# TC364_MainBoard_Power_V2_0.net
KiCad netlist of a schematic drawn in Altium Designer
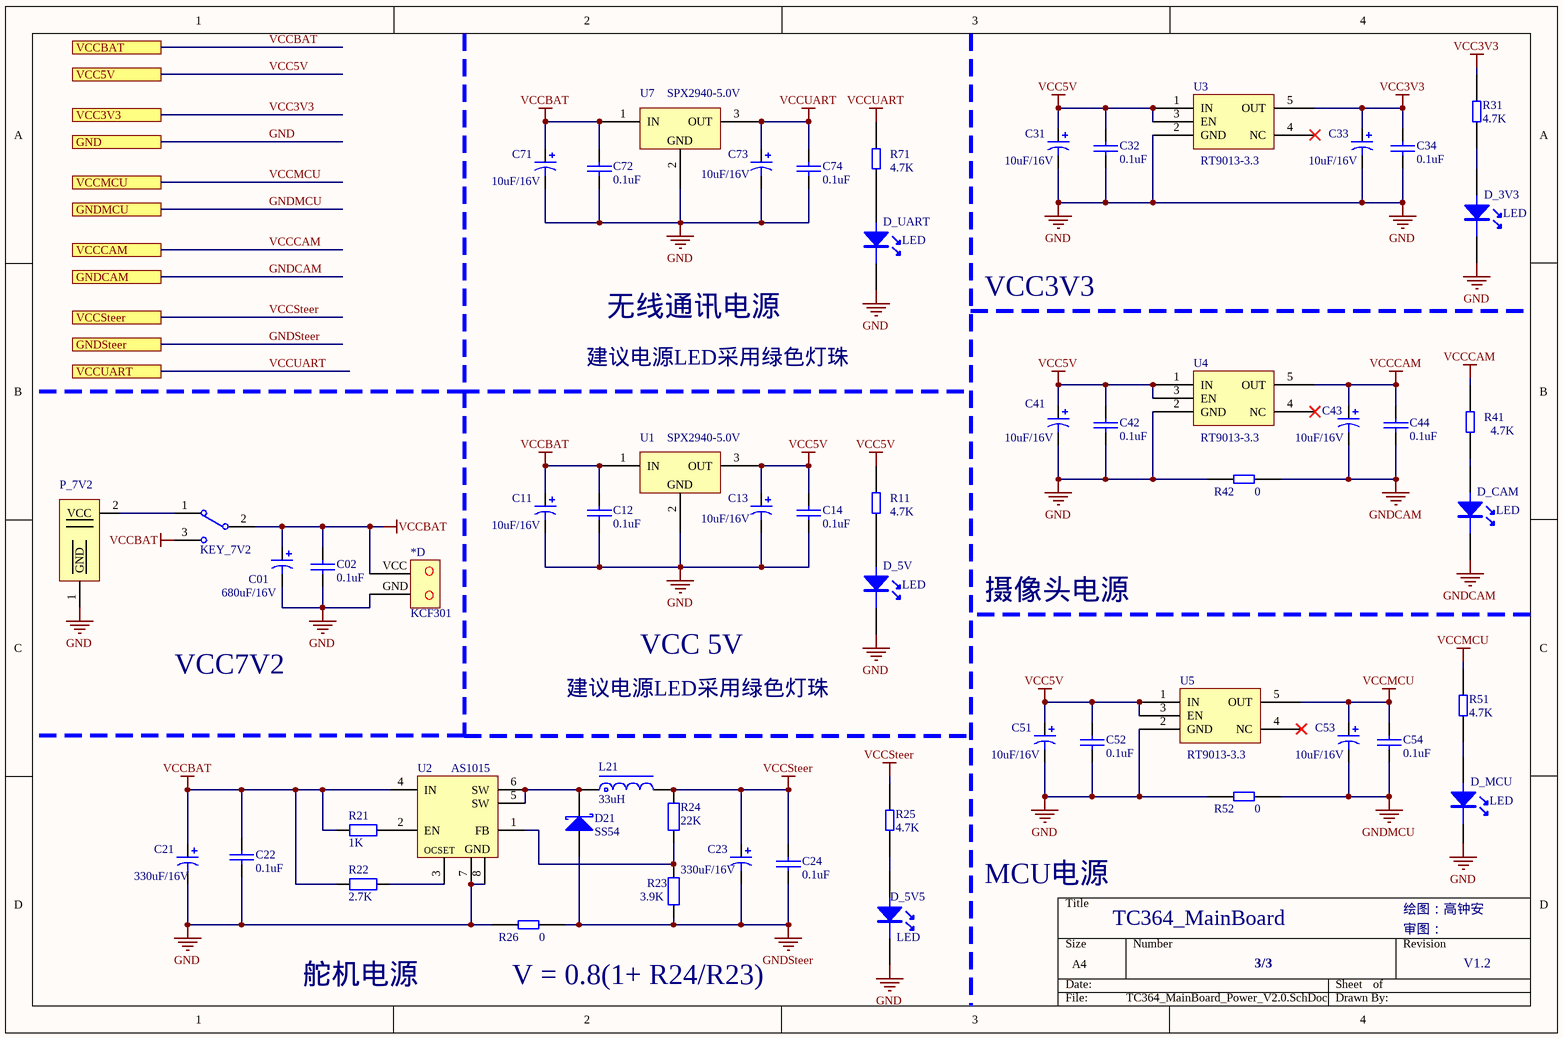
[diagram p0: TC364_MainBoard_Power_V2.0.SchDoc]

(export (version "E")
  (design (tool "Eeschema 10.0.6"))
  (components
    (comp (ref "*") (value "KCF301") (footprint "KF301-2P") (libsource (lib "BaseLib_SCH") (part "KCF301")))
    (comp (ref "C01")
      (value "680uF/16V")
      (footprint "CAP 3.5*8*11.5 - GD")
      (description "Polarized Capacitor (Radial)")
      (fields (field (name "PUBLISHER") "Altium Limited"))
      (libsource (lib "Miscellaneous Devices") (part "Cap Pol1"))
    )
    (comp (ref "C02")
      (value "0.1uF")
      (footprint "0805C")
      (description "Capacitor")
      (libsource (lib "Protel99Lib_SCH") (part "CAP"))
    )
    (comp (ref "C11")
      (value "10uF/16V")
      (footprint "CASE-A_3216")
      (description "Polarized Capacitor (Radial)")
      (fields (field (name "PUBLISHER") "Altium Limited"))
      (libsource (lib "Miscellaneous Devices") (part "Cap Pol1"))
    )
    (comp (ref "C12")
      (value "0.1uF")
      (footprint "0805C")
      (description "Capacitor")
      (libsource (lib "Protel99Lib_SCH") (part "CAP"))
    )
    (comp (ref "C13")
      (value "10uF/16V")
      (footprint "CASE-A_3216")
      (description "Polarized Capacitor (Radial)")
      (fields (field (name "PUBLISHER") "Altium Limited"))
      (libsource (lib "Miscellaneous Devices") (part "Cap Pol1"))
    )
    (comp (ref "C14")
      (value "0.1uF")
      (footprint "0805C")
      (description "Capacitor")
      (libsource (lib "Protel99Lib_SCH") (part "CAP"))
    )
    (comp (ref "C21")
      (value "330uF/16V")
      (footprint "CAP 2.5*6.3*11.2 - BK")
      (description "Polarized Capacitor (Radial)")
      (fields (field (name "PUBLISHER") "Altium Limited"))
      (libsource (lib "Miscellaneous Devices") (part "Cap Pol1"))
    )
    (comp (ref "C22")
      (value "0.1uF")
      (footprint "0805C")
      (description "Capacitor")
      (libsource (lib "Protel99Lib_SCH") (part "CAP"))
    )
    (comp (ref "C23")
      (value "330uF/16V")
      (footprint "CAP 2.5*6.3*11.2 - BK")
      (description "Polarized Capacitor (Radial)")
      (fields (field (name "PUBLISHER") "Altium Limited"))
      (libsource (lib "Miscellaneous Devices") (part "Cap Pol1"))
    )
    (comp (ref "C24")
      (value "0.1uF")
      (footprint "0805C")
      (description "Capacitor")
      (libsource (lib "Protel99Lib_SCH") (part "CAP"))
    )
    (comp (ref "C31")
      (value "10uF/16V")
      (footprint "CASE-A_3216")
      (description "Polarized Capacitor (Radial)")
      (fields (field (name "PUBLISHER") "Altium Limited"))
      (libsource (lib "Miscellaneous Devices") (part "Cap Pol1"))
    )
    (comp (ref "C32")
      (value "0.1uF")
      (footprint "0805C")
      (description "Capacitor")
      (libsource (lib "Protel99Lib_SCH") (part "CAP"))
    )
    (comp (ref "C33")
      (value "10uF/16V")
      (footprint "CASE-A_3216")
      (description "Polarized Capacitor (Radial)")
      (fields (field (name "PUBLISHER") "Altium Limited"))
      (libsource (lib "Miscellaneous Devices") (part "Cap Pol1"))
    )
    (comp (ref "C34")
      (value "0.1uF")
      (footprint "0805C")
      (description "Capacitor")
      (libsource (lib "Protel99Lib_SCH") (part "CAP"))
    )
    (comp (ref "C41")
      (value "10uF/16V")
      (footprint "CASE-A_3216")
      (description "Polarized Capacitor (Radial)")
      (fields (field (name "PUBLISHER") "Altium Limited"))
      (libsource (lib "Miscellaneous Devices") (part "Cap Pol1"))
    )
    (comp (ref "C42")
      (value "0.1uF")
      (footprint "0805C")
      (description "Capacitor")
      (libsource (lib "Protel99Lib_SCH") (part "CAP"))
    )
    (comp (ref "C43")
      (value "10uF/16V")
      (footprint "CASE-A_3216")
      (description "Polarized Capacitor (Radial)")
      (fields (field (name "PUBLISHER") "Altium Limited"))
      (libsource (lib "Miscellaneous Devices") (part "Cap Pol1"))
    )
    (comp (ref "C44")
      (value "0.1uF")
      (footprint "0805C")
      (description "Capacitor")
      (libsource (lib "Protel99Lib_SCH") (part "CAP"))
    )
    (comp (ref "C51")
      (value "10uF/16V")
      (footprint "CASE-A_3216")
      (description "Polarized Capacitor (Radial)")
      (fields (field (name "PUBLISHER") "Altium Limited"))
      (libsource (lib "Miscellaneous Devices") (part "Cap Pol1"))
    )
    (comp (ref "C52")
      (value "0.1uF")
      (footprint "0805C")
      (description "Capacitor")
      (libsource (lib "Protel99Lib_SCH") (part "CAP"))
    )
    (comp (ref "C53")
      (value "10uF/16V")
      (footprint "CASE-A_3216")
      (description "Polarized Capacitor (Radial)")
      (fields (field (name "PUBLISHER") "Altium Limited"))
      (libsource (lib "Miscellaneous Devices") (part "Cap Pol1"))
    )
    (comp (ref "C54")
      (value "0.1uF")
      (footprint "0805C")
      (description "Capacitor")
      (libsource (lib "Protel99Lib_SCH") (part "CAP"))
    )
    (comp (ref "C71")
      (value "10uF/16V")
      (footprint "CASE-A_3216")
      (description "Polarized Capacitor (Radial)")
      (fields (field (name "PUBLISHER") "Altium Limited"))
      (libsource (lib "Miscellaneous Devices") (part "Cap Pol1"))
    )
    (comp (ref "C72")
      (value "0.1uF")
      (footprint "0805C")
      (description "Capacitor")
      (libsource (lib "Protel99Lib_SCH") (part "CAP"))
    )
    (comp (ref "C73")
      (value "10uF/16V")
      (footprint "CASE-A_3216")
      (description "Polarized Capacitor (Radial)")
      (fields (field (name "PUBLISHER") "Altium Limited"))
      (libsource (lib "Miscellaneous Devices") (part "Cap Pol1"))
    )
    (comp (ref "C74")
      (value "0.1uF")
      (footprint "0805C")
      (description "Capacitor")
      (libsource (lib "Protel99Lib_SCH") (part "CAP"))
    )
    (comp (ref "D21")
      (value "SS54")
      (footprint "SMA")
      (description "肖特基二极管")
      (libsource (lib "0.2 -  二极管-整流桥") (part "SS34"))
    )
    (comp (ref "D_3V3")
      (value "LED")
      (footprint "0805_LED_S1")
      (description "发光二极管")
      (libsource (lib "jianing") (part "LED"))
    )
    (comp (ref "D_5V")
      (value "LED")
      (footprint "0805_LED_S1")
      (description "发光二极管")
      (libsource (lib "jianing") (part "LED"))
    )
    (comp (ref "D_5V5")
      (value "LED")
      (footprint "0805_LED_S1")
      (description "发光二极管")
      (libsource (lib "jianing") (part "LED"))
    )
    (comp (ref "D_CAM")
      (value "LED")
      (footprint "0805_LED_S1")
      (description "发光二极管")
      (libsource (lib "jianing") (part "LED"))
    )
    (comp (ref "D_MCU")
      (value "LED")
      (footprint "0805_LED_S1")
      (description "发光二极管")
      (libsource (lib "jianing") (part "LED"))
    )
    (comp (ref "D_UART")
      (value "LED")
      (footprint "0805_LED_S1")
      (description "发光二极管")
      (libsource (lib "jianing") (part "LED"))
    )
    (comp (ref "KEY_7V2")
      (value "SS-12F23")
      (footprint "KEY_7V2")
      (description "1路波动开关")
      (fields (field (name "版权归属") "封装库来自淘宝 ID：黄晶宝石"))
      (libsource (lib "0.7 - 常用按键-开关") (part "SSW-1P"))
    )
    (comp (ref "L21")
      (value "33uH")
      (footprint "7*7 L")
      (description "功率屏蔽电感")
      (fields (field (name "版权归属") "封装库来自淘宝 ID：黄晶宝石"))
      (libsource (lib "0.1 - 电阻-电容-电感") (part "L-CDRH"))
    )
    (comp (ref "P_7V2")
      (value "T_Type_Adapter")
      (footprint "T_Type_Adapter")
      (libsource (lib "Schlib1") (part "T_Type_Adapter"))
    )
    (comp (ref "R11") (value "4.7K") (footprint "0805R") (libsource (lib "BaseLib_SCH") (part "RES")))
    (comp (ref "R21")
      (value "1K")
      (footprint "0805R")
      (description "贴片电阻")
      (fields (field (name "版权归属") "源创客"))
      (libsource (lib "jianing") (part "RES"))
    )
    (comp (ref "R22")
      (value "2.7K")
      (footprint "0805R")
      (description "贴片电阻")
      (fields (field (name "版权归属") "源创客"))
      (libsource (lib "jianing") (part "RES"))
    )
    (comp (ref "R23")
      (value "3.9K")
      (footprint "0805R")
      (description "贴片电阻")
      (fields (field (name "版权归属") "源创客"))
      (libsource (lib "jianing") (part "RES"))
    )
    (comp (ref "R24")
      (value "22K")
      (footprint "0805R")
      (description "贴片电阻")
      (fields (field (name "版权归属") "源创客"))
      (libsource (lib "jianing") (part "RES"))
    )
    (comp (ref "R25") (value "4.7K") (footprint "0805R") (libsource (lib "BaseLib_SCH") (part "RES")))
    (comp (ref "R26") (value "0") (footprint "0805R") (libsource (lib "BaseLib_SCH") (part "RES")))
    (comp (ref "R31") (value "4.7K") (footprint "0805R") (libsource (lib "BaseLib_SCH") (part "RES")))
    (comp (ref "R41") (value "4.7K") (footprint "0805R") (libsource (lib "BaseLib_SCH") (part "RES")))
    (comp (ref "R42") (value "0") (footprint "0805R") (libsource (lib "BaseLib_SCH") (part "RES")))
    (comp (ref "R51") (value "4.7K") (footprint "0805R") (libsource (lib "BaseLib_SCH") (part "RES")))
    (comp (ref "R52") (value "0") (footprint "0805R") (libsource (lib "BaseLib_SCH") (part "RES")))
    (comp (ref "R71") (value "4.7K") (footprint "0805R") (libsource (lib "BaseLib_SCH") (part "RES")))
    (comp (ref "U1")
      (value "SPX2940-5.0V")
      (footprint "TO-220(TO-220-3)")
      (description "5V稳压芯片")
      (fields (field (name "版权归属") "封装库来自淘宝 ID：黄晶宝石"))
      (libsource (lib "1.1 - 电源类芯片") (part "LM2940"))
    )
    (comp (ref "U2")
      (value "AS1015")
      (footprint "SOP-8_150mil")
      (description "可调升压芯片")
      (libsource (lib "1.0 - 常见芯片") (part "AS1015"))
    )
    (comp (ref "U3")
      (value "RT9013-3.3")
      (footprint "SOT-23-5")
      (libsource (lib "jianing") (part "RT9013-3.3"))
    )
    (comp (ref "U4")
      (value "RT9013-3.3")
      (footprint "SOT-23-5")
      (libsource (lib "jianing") (part "RT9013-3.3"))
    )
    (comp (ref "U5")
      (value "RT9013-3.3")
      (footprint "SOT-23-5")
      (libsource (lib "jianing") (part "RT9013-3.3"))
    )
    (comp (ref "U7")
      (value "SPX2940-5.0V")
      (footprint "TO-220(TO-220-3)")
      (description "5V稳压芯片")
      (fields (field (name "版权归属") "封装库来自淘宝 ID：黄晶宝石"))
      (libsource (lib "1.1 - 电源类芯片") (part "LM2940"))
    )
  )
  (nets
    (net (code "1") (name "GND") (class "Default")
      (node (ref "C01") (pin "2") (pinfunction "2_2") (pintype "passive"))
      (node (ref "C02") (pin "2") (pinfunction "2_2") (pintype "passive"))
      (node (ref "C11") (pin "2") (pinfunction "2_2") (pintype "passive"))
      (node (ref "C12") (pin "2") (pinfunction "2_2") (pintype "passive"))
      (node (ref "C13") (pin "2") (pinfunction "2_2") (pintype "passive"))
      (node (ref "C14") (pin "2") (pinfunction "2_2") (pintype "passive"))
      (node (ref "C21") (pin "2") (pinfunction "2_2") (pintype "passive"))
      (node (ref "C22") (pin "2") (pinfunction "2_2") (pintype "passive"))
      (node (ref "C31") (pin "2") (pinfunction "2_2") (pintype "passive"))
      (node (ref "C32") (pin "2") (pinfunction "2_2") (pintype "passive"))
      (node (ref "C33") (pin "2") (pinfunction "2_2") (pintype "passive"))
      (node (ref "C34") (pin "2") (pinfunction "2_2") (pintype "passive"))
      (node (ref "C41") (pin "2") (pinfunction "2_2") (pintype "passive"))
      (node (ref "C42") (pin "2") (pinfunction "2_2") (pintype "passive"))
      (node (ref "C51") (pin "2") (pinfunction "2_2") (pintype "passive"))
      (node (ref "C52") (pin "2") (pinfunction "2_2") (pintype "passive"))
      (node (ref "C71") (pin "2") (pinfunction "2_2") (pintype "passive"))
      (node (ref "C72") (pin "2") (pinfunction "2_2") (pintype "passive"))
      (node (ref "C73") (pin "2") (pinfunction "2_2") (pintype "passive"))
      (node (ref "C74") (pin "2") (pinfunction "2_2") (pintype "passive"))
      (node (ref "D_3V3") (pin "K") (pinfunction "2_K") (pintype "passive"))
      (node (ref "D_5V") (pin "K") (pinfunction "2_K") (pintype "passive"))
      (node (ref "D_5V5") (pin "K") (pinfunction "2_K") (pintype "passive"))
      (node (ref "D_UART") (pin "K") (pinfunction "2_K") (pintype "passive"))
      (node (ref "P_7V2") (pin "1") (pinfunction "GND_1") (pintype "passive"))
      (node (ref "R26") (pin "2") (pinfunction "2_2") (pintype "passive"))
      (node (ref "R42") (pin "2") (pinfunction "2_2") (pintype "passive"))
      (node (ref "R52") (pin "2") (pinfunction "2_2") (pintype "passive"))
      (node (ref "U1") (pin "2") (pinfunction "GND_2") (pintype "power_in"))
      (node (ref "U2") (pin "7") (pinfunction "GND_7") (pintype "power_in"))
      (node (ref "U2") (pin "8") (pinfunction "GND_8") (pintype "power_in"))
      (node (ref "U3") (pin "2") (pinfunction "GND_2") (pintype "passive"))
      (node (ref "U4") (pin "2") (pinfunction "GND_2") (pintype "passive"))
      (node (ref "U5") (pin "2") (pinfunction "GND_2") (pintype "passive"))
      (node (ref "U7") (pin "2") (pinfunction "GND_2") (pintype "power_in"))
    )
    (net (code "2") (name "GNDCAM") (class "Default")
      (node (ref "C43") (pin "2") (pinfunction "2_2") (pintype "passive"))
      (node (ref "C44") (pin "2") (pinfunction "2_2") (pintype "passive"))
      (node (ref "D_CAM") (pin "K") (pinfunction "2_K") (pintype "passive"))
      (node (ref "R42") (pin "1") (pinfunction "1_1") (pintype "passive"))
    )
    (net (code "3") (name "GNDMCU") (class "Default")
      (node (ref "C53") (pin "2") (pinfunction "2_2") (pintype "passive"))
      (node (ref "C54") (pin "2") (pinfunction "2_2") (pintype "passive"))
      (node (ref "R52") (pin "1") (pinfunction "1_1") (pintype "passive"))
    )
    (net (code "4") (name "GNDSteer") (class "Default")
      (node (ref "C23") (pin "2") (pinfunction "2_2") (pintype "passive"))
      (node (ref "C24") (pin "2") (pinfunction "2_2") (pintype "passive"))
      (node (ref "D21") (pin "1") (pinfunction "A_1") (pintype "passive"))
      (node (ref "R23") (pin "2") (pinfunction "2_2") (pintype "passive"))
      (node (ref "R26") (pin "1") (pinfunction "1_1") (pintype "passive"))
    )
    (net (code "5") (name "Net-(D21-K)") (class "Default")
      (node (ref "D21") (pin "2") (pinfunction "K_2") (pintype "passive"))
      (node (ref "L21") (pin "1") (pinfunction "1_1") (pintype "passive"))
      (node (ref "U2") (pin "5") (pinfunction "SW_5") (pintype "power_in"))
      (node (ref "U2") (pin "6") (pinfunction "SW_6") (pintype "power_in"))
    )
    (net (code "6") (name "Net-(D_3V3-1)") (class "Default")
      (node (ref "D_3V3") (pin "A") (pinfunction "1_A") (pintype "passive"))
      (node (ref "R31") (pin "2") (pinfunction "2_2") (pintype "passive"))
    )
    (net (code "7") (name "Net-(D_5V-1)") (class "Default")
      (node (ref "D_5V") (pin "A") (pinfunction "1_A") (pintype "passive"))
      (node (ref "R11") (pin "2") (pinfunction "2_2") (pintype "passive"))
    )
    (net (code "8") (name "Net-(D_5V5-1)") (class "Default")
      (node (ref "D_5V5") (pin "A") (pinfunction "1_A") (pintype "passive"))
      (node (ref "R25") (pin "2") (pinfunction "2_2") (pintype "passive"))
    )
    (net (code "9") (name "Net-(D_CAM-1)") (class "Default")
      (node (ref "D_CAM") (pin "A") (pinfunction "1_A") (pintype "passive"))
      (node (ref "R41") (pin "2") (pinfunction "2_2") (pintype "passive"))
    )
    (net (code "10") (name "Net-(D_MCU-1)") (class "Default")
      (node (ref "D_MCU") (pin "A") (pinfunction "1_A") (pintype "passive"))
      (node (ref "R51") (pin "2") (pinfunction "2_2") (pintype "passive"))
    )
    (net (code "11") (name "Net-(D_UART-1)") (class "Default")
      (node (ref "D_UART") (pin "A") (pinfunction "1_A") (pintype "passive"))
      (node (ref "R71") (pin "2") (pinfunction "2_2") (pintype "passive"))
    )
    (net (code "12") (name "Net-(P_7V2-VCC)") (class "Default")
      (node (ref "KEY_7V2") (pin "1") (pinfunction "1_1") (pintype "passive"))
      (node (ref "P_7V2") (pin "2") (pinfunction "VCC_2") (pintype "passive"))
    )
    (net (code "13") (name "Net-(U2-EN)") (class "Default")
      (node (ref "R21") (pin "1") (pinfunction "1_1") (pintype "passive"))
      (node (ref "U2") (pin "2") (pinfunction "EN_2") (pintype "power_in"))
    )
    (net (code "14") (name "Net-(U2-FB)") (class "Default")
      (node (ref "R23") (pin "1") (pinfunction "1_1") (pintype "passive"))
      (node (ref "R24") (pin "2") (pinfunction "2_2") (pintype "passive"))
      (node (ref "U2") (pin "1") (pinfunction "FB_1") (pintype "power_in"))
    )
    (net (code "15") (name "Net-(U2-OCSET)") (class "Default")
      (node (ref "R22") (pin "1") (pinfunction "1_1") (pintype "passive"))
      (node (ref "U2") (pin "3") (pinfunction "OCSET_3") (pintype "power_in"))
    )
    (net (code "16") (name "VCC3V3") (class "Default")
      (node (ref "C33") (pin "1") (pinfunction "1_1") (pintype "passive"))
      (node (ref "C34") (pin "1") (pinfunction "1_1") (pintype "passive"))
      (node (ref "R31") (pin "1") (pinfunction "1_1") (pintype "passive"))
      (node (ref "U3") (pin "5") (pinfunction "OUT_5") (pintype "passive"))
    )
    (net (code "17") (name "VCC5V") (class "Default")
      (node (ref "C13") (pin "1") (pinfunction "1_1") (pintype "passive"))
      (node (ref "C14") (pin "1") (pinfunction "1_1") (pintype "passive"))
      (node (ref "C31") (pin "1") (pinfunction "1_1") (pintype "passive"))
      (node (ref "C32") (pin "1") (pinfunction "1_1") (pintype "passive"))
      (node (ref "C41") (pin "1") (pinfunction "1_1") (pintype "passive"))
      (node (ref "C42") (pin "1") (pinfunction "1_1") (pintype "passive"))
      (node (ref "C51") (pin "1") (pinfunction "1_1") (pintype "passive"))
      (node (ref "C52") (pin "1") (pinfunction "1_1") (pintype "passive"))
      (node (ref "R11") (pin "1") (pinfunction "1_1") (pintype "passive"))
      (node (ref "U1") (pin "3") (pinfunction "OUT_3") (pintype "power_in"))
      (node (ref "U3") (pin "1") (pinfunction "IN_1") (pintype "passive"))
      (node (ref "U3") (pin "3") (pinfunction "EN_3") (pintype "passive"))
      (node (ref "U4") (pin "1") (pinfunction "IN_1") (pintype "passive"))
      (node (ref "U4") (pin "3") (pinfunction "EN_3") (pintype "passive"))
      (node (ref "U5") (pin "1") (pinfunction "IN_1") (pintype "passive"))
      (node (ref "U5") (pin "3") (pinfunction "EN_3") (pintype "passive"))
    )
    (net (code "18") (name "VCCBAT") (class "Default")
      (node (ref "C01") (pin "1") (pinfunction "1_1") (pintype "passive"))
      (node (ref "C02") (pin "1") (pinfunction "1_1") (pintype "passive"))
      (node (ref "C11") (pin "1") (pinfunction "1_1") (pintype "passive"))
      (node (ref "C12") (pin "1") (pinfunction "1_1") (pintype "passive"))
      (node (ref "C21") (pin "1") (pinfunction "1_1") (pintype "passive"))
      (node (ref "C22") (pin "1") (pinfunction "1_1") (pintype "passive"))
      (node (ref "C71") (pin "1") (pinfunction "1_1") (pintype "passive"))
      (node (ref "C72") (pin "1") (pinfunction "1_1") (pintype "passive"))
      (node (ref "KEY_7V2") (pin "2") (pinfunction "2_2") (pintype "passive"))
      (node (ref "KEY_7V2") (pin "3") (pinfunction "3_3") (pintype "passive"))
      (node (ref "R21") (pin "2") (pinfunction "2_2") (pintype "passive"))
      (node (ref "R22") (pin "2") (pinfunction "2_2") (pintype "passive"))
      (node (ref "U1") (pin "1") (pinfunction "IN_1") (pintype "power_in"))
      (node (ref "U2") (pin "4") (pinfunction "IN_4") (pintype "power_in"))
      (node (ref "U7") (pin "1") (pinfunction "IN_1") (pintype "power_in"))
    )
    (net (code "19") (name "VCCCAM") (class "Default")
      (node (ref "C43") (pin "1") (pinfunction "1_1") (pintype "passive"))
      (node (ref "C44") (pin "1") (pinfunction "1_1") (pintype "passive"))
      (node (ref "R41") (pin "1") (pinfunction "1_1") (pintype "passive"))
      (node (ref "U4") (pin "5") (pinfunction "OUT_5") (pintype "passive"))
    )
    (net (code "20") (name "VCCMCU") (class "Default")
      (node (ref "C53") (pin "1") (pinfunction "1_1") (pintype "passive"))
      (node (ref "C54") (pin "1") (pinfunction "1_1") (pintype "passive"))
      (node (ref "R51") (pin "1") (pinfunction "1_1") (pintype "passive"))
      (node (ref "U5") (pin "5") (pinfunction "OUT_5") (pintype "passive"))
    )
    (net (code "21") (name "VCCSteer") (class "Default")
      (node (ref "C23") (pin "1") (pinfunction "1_1") (pintype "passive"))
      (node (ref "C24") (pin "1") (pinfunction "1_1") (pintype "passive"))
      (node (ref "L21") (pin "2") (pinfunction "2_2") (pintype "passive"))
      (node (ref "R24") (pin "1") (pinfunction "1_1") (pintype "passive"))
      (node (ref "R25") (pin "1") (pinfunction "1_1") (pintype "passive"))
    )
    (net (code "22") (name "VCCUART") (class "Default")
      (node (ref "C73") (pin "1") (pinfunction "1_1") (pintype "passive"))
      (node (ref "C74") (pin "1") (pinfunction "1_1") (pintype "passive"))
      (node (ref "R71") (pin "1") (pinfunction "1_1") (pintype "passive"))
      (node (ref "U7") (pin "3") (pinfunction "OUT_3") (pintype "power_in"))
    )
    (net (code "23") (name "unconnected-(*D-0-PadVCC)") (class "Default")
      (node (ref "*") (pin "VCC") (pinfunction "0_VCC") (pintype "passive"))
    )
    (net (code "24") (name "unconnected-(*D-1-PadGND)") (class "Default")
      (node (ref "*") (pin "GND") (pinfunction "1_GND") (pintype "passive"))
    )
    (net (code "25") (name "unconnected-(D_MCU-2-PadK)") (class "Default")
      (node (ref "D_MCU") (pin "K") (pinfunction "2_K") (pintype "passive"))
    )
    (net (code "26") (name "unconnected-(U3-NC-Pad4)") (class "Default")
      (node (ref "U3") (pin "4") (pinfunction "NC_4") (pintype "passive+no_connect"))
    )
    (net (code "27") (name "unconnected-(U4-NC-Pad4)") (class "Default")
      (node (ref "U4") (pin "4") (pinfunction "NC_4") (pintype "passive+no_connect"))
    )
    (net (code "28") (name "unconnected-(U5-NC-Pad4)") (class "Default")
      (node (ref "U5") (pin "4") (pinfunction "NC_4") (pintype "passive+no_connect"))
    )
  )
)
